# LAN.net
KiCad netlist of a schematic drawn in Altium Designer
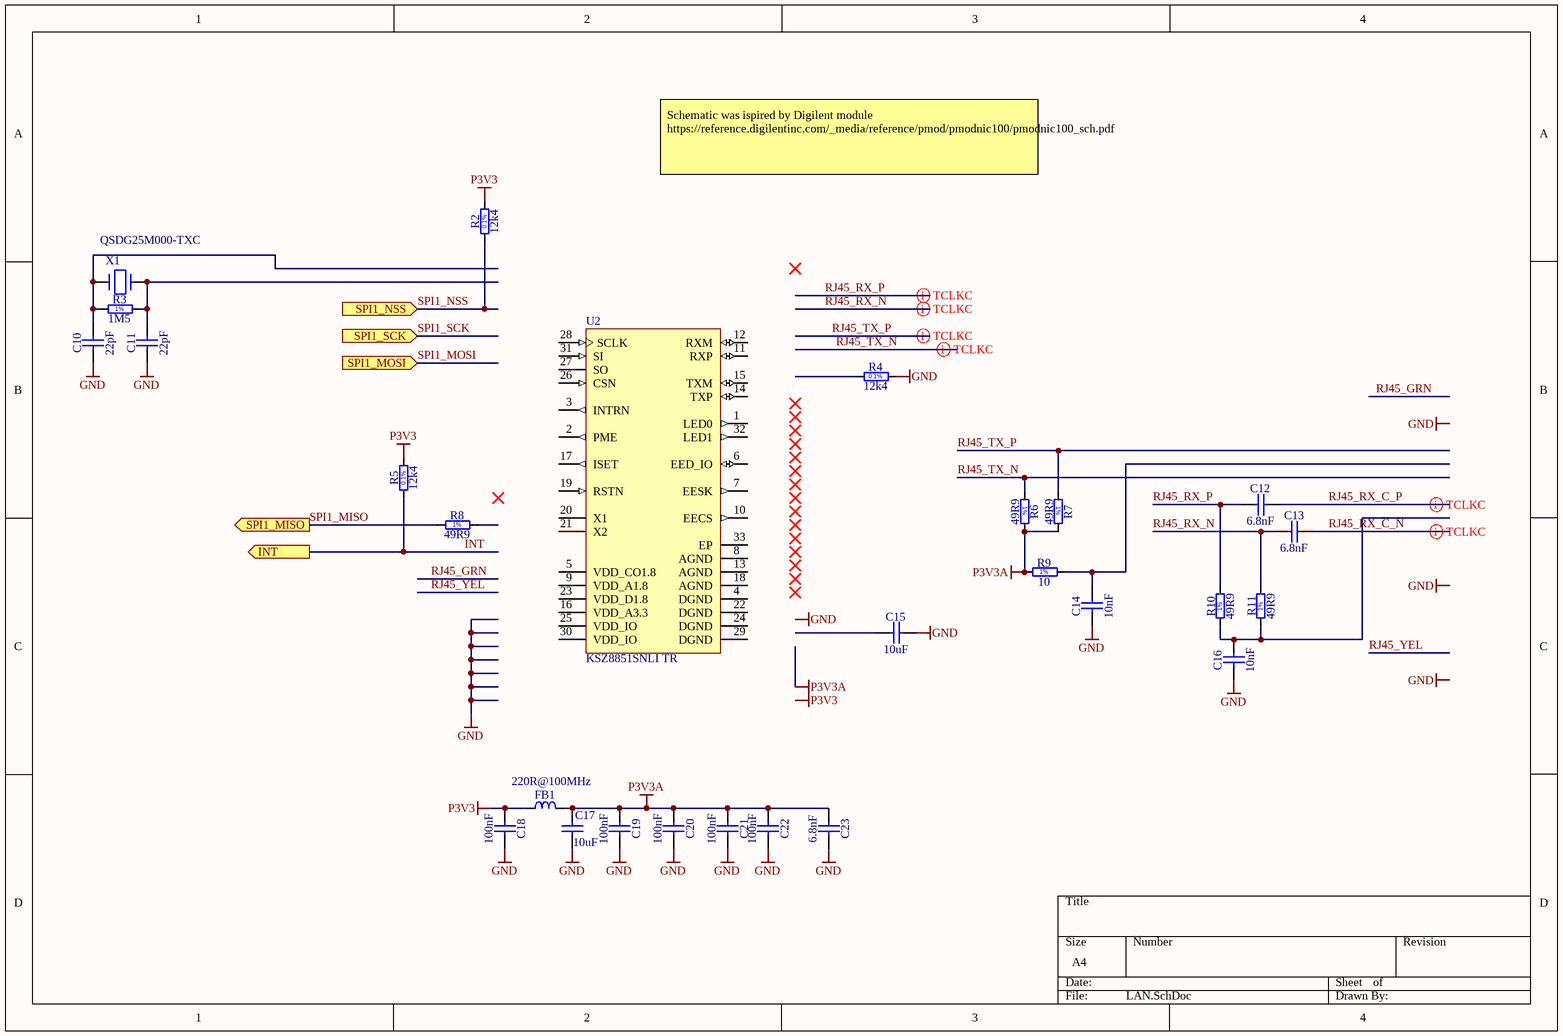
[diagram p0: LAN.SchDoc]

(export (version "E")
  (design (tool "Eeschema 10.0.6"))
  (components
    (comp (ref "C10")
      (value "22pF")
      (footprint "CAPC1005X55N")
      (description "Non-polarised capacitor")
      (fields
        (field (name "PART NUMBER") "CC0402_22PF_50V_5%_NP0")
        (field (name "VOLTAGE") "50V")
        (field (name "AUTHOR") "CERN DEM JLC")
      )
      (libsource (lib "Capacitors") (part "Capacitor - non polarized"))
    )
    (comp (ref "C11")
      (value "22pF")
      (footprint "CAPC1005X55N")
      (description "Non-polarised capacitor")
      (fields
        (field (name "PART NUMBER") "CC0402_22PF_50V_5%_NP0")
        (field (name "VOLTAGE") "50V")
        (field (name "AUTHOR") "CERN DEM JLC")
      )
      (libsource (lib "Capacitors") (part "Capacitor - non polarized"))
    )
    (comp (ref "C12")
      (value "6.8nF")
      (footprint "CAPC1608X87N")
      (description "Non-polarised capacitor")
      (fields
        (field (name "PART NUMBER") "CC0603_6.8NF_25V_1%_C0G")
        (field (name "VOLTAGE") "25V")
        (field (name "AUTHOR") "CERN DEM JLC")
      )
      (libsource (lib "Capacitors") (part "Capacitor - non polarized"))
    )
    (comp (ref "C13")
      (value "6.8nF")
      (footprint "CAPC1608X87N")
      (description "Non-polarised capacitor")
      (fields
        (field (name "PART NUMBER") "CC0603_6.8NF_25V_1%_C0G")
        (field (name "VOLTAGE") "25V")
        (field (name "AUTHOR") "CERN DEM JLC")
      )
      (libsource (lib "Capacitors") (part "Capacitor - non polarized"))
    )
    (comp (ref "C14")
      (value "10nF")
      (footprint "CAPC1608X87N")
      (description "Non-polarised capacitor")
      (fields
        (field (name "PART NUMBER") "CC0603_10NF_50V_5%_C0G")
        (field (name "VOLTAGE") "50V")
        (field (name "AUTHOR") "CERN DEM JLC")
      )
      (libsource (lib "Capacitors") (part "Capacitor - non polarized"))
    )
    (comp (ref "C15")
      (value "10uF")
      (footprint "CAPC1608X80N")
      (description "Non-polarised capacitor")
      (fields
        (field (name "PART NUMBER") "CC0603_10UF_16V_20%_X5R")
        (field (name "VOLTAGE") "16V")
        (field (name "AUTHOR") "CERN DEM MR")
      )
      (libsource (lib "Capacitors") (part "Capacitor - non polarized"))
    )
    (comp (ref "C16")
      (value "10nF")
      (footprint "CAPC1608X87N")
      (description "Non-polarised capacitor")
      (fields
        (field (name "PART NUMBER") "CC0603_10NF_50V_5%_C0G")
        (field (name "VOLTAGE") "50V")
        (field (name "AUTHOR") "CERN DEM JLC")
      )
      (libsource (lib "Capacitors") (part "Capacitor - non polarized"))
    )
    (comp (ref "C17")
      (value "10uF")
      (footprint "CAPC2012X135N")
      (description "Non-polarised capacitor")
      (fields
        (field (name "PART NUMBER") "CC0805_10UF_10V_10%_X7R")
        (field (name "VOLTAGE") "10V")
        (field (name "AUTHOR") "CERN DEM JLC")
      )
      (libsource (lib "Capacitors") (part "Capacitor - non polarized"))
    )
    (comp (ref "C18")
      (value "100nF")
      (footprint "CAPC1005X55N")
      (description "Non-polarised capacitor")
      (fields
        (field (name "PART NUMBER") "CC0402_100NF_16V_10%_X7R")
        (field (name "VOLTAGE") "16V")
        (field (name "AUTHOR") "CERN DEM JLC")
      )
      (libsource (lib "Capacitors") (part "Capacitor - non polarized"))
    )
    (comp (ref "C19")
      (value "100nF")
      (footprint "CAPC1005X55N")
      (description "Non-polarised capacitor")
      (fields
        (field (name "PART NUMBER") "CC0402_100NF_16V_10%_X7R")
        (field (name "VOLTAGE") "16V")
        (field (name "AUTHOR") "CERN DEM JLC")
      )
      (libsource (lib "Capacitors") (part "Capacitor - non polarized"))
    )
    (comp (ref "C20")
      (value "100nF")
      (footprint "CAPC1005X55N")
      (description "Non-polarised capacitor")
      (fields
        (field (name "PART NUMBER") "CC0402_100NF_16V_10%_X7R")
        (field (name "VOLTAGE") "16V")
        (field (name "AUTHOR") "CERN DEM JLC")
      )
      (libsource (lib "Capacitors") (part "Capacitor - non polarized"))
    )
    (comp (ref "C21")
      (value "100nF")
      (footprint "CAPC1005X55N")
      (description "Non-polarised capacitor")
      (fields
        (field (name "PART NUMBER") "CC0402_100NF_16V_10%_X7R")
        (field (name "VOLTAGE") "16V")
        (field (name "AUTHOR") "CERN DEM JLC")
      )
      (libsource (lib "Capacitors") (part "Capacitor - non polarized"))
    )
    (comp (ref "C22")
      (value "100nF")
      (footprint "CAPC1005X55N")
      (description "Non-polarised capacitor")
      (fields
        (field (name "PART NUMBER") "CC0402_100NF_16V_10%_X7R")
        (field (name "VOLTAGE") "16V")
        (field (name "AUTHOR") "CERN DEM JLC")
      )
      (libsource (lib "Capacitors") (part "Capacitor - non polarized"))
    )
    (comp (ref "C23")
      (value "6.8nF")
      (footprint "CAPC1608X87N")
      (description "Non-polarised capacitor")
      (fields
        (field (name "PART NUMBER") "CC0603_6.8NF_25V_1%_C0G")
        (field (name "VOLTAGE") "25V")
        (field (name "AUTHOR") "CERN DEM JLC")
      )
      (libsource (lib "Capacitors") (part "Capacitor - non polarized"))
    )
    (comp (ref "FB1")
      (value "220R@100MHz")
      (footprint "INDC2012X105N")
      (description "Inductor")
      (fields
        (field (name "PART NUMBER") "IND0805_MURATA_BLM21PG221SN1D")
        (field (name "POWER") "2A")
        (field (name "AUTHOR") "CERN DEM JLC")
      )
      (libsource (lib "Inductors & Transformers") (part "Inductor"))
    )
    (comp (ref "R2")
      (value "12k4")
      (footprint "RESC1608X55N")
      (description "Resistor - 0.1%")
      (fields
        (field (name "PART NUMBER") "R0603_12K4_0.1%_0.063W_10PPM")
        (field (name "POWER") "0.063W")
        (field (name "AUTHOR") "CERN DEM JLC")
      )
      (libsource (lib "Resistors") (part "Resistor - 0.1%"))
    )
    (comp (ref "R3")
      (value "1M5")
      (footprint "RESC1005X40N")
      (description "Resistor - 1%")
      (fields
        (field (name "PART NUMBER") "R0402_1M5_1%_0.0625W_100PPM")
        (field (name "POWER") "0.0625W")
        (field (name "AUTHOR") "CERN DEM JLC")
      )
      (libsource (lib "Resistors") (part "Resistor - 1%"))
    )
    (comp (ref "R4")
      (value "12k4")
      (footprint "RESC1608X55N")
      (description "Resistor - 0.1%")
      (fields
        (field (name "PART NUMBER") "R0603_12K4_0.1%_0.063W_10PPM")
        (field (name "POWER") "0.063W")
        (field (name "AUTHOR") "CERN DEM JLC")
      )
      (libsource (lib "Resistors") (part "Resistor - 0.1%"))
    )
    (comp (ref "R5")
      (value "12k4")
      (footprint "RESC1608X55N")
      (description "Resistor - 0.1%")
      (fields
        (field (name "PART NUMBER") "R0603_12K4_0.1%_0.063W_10PPM")
        (field (name "POWER") "0.063W")
        (field (name "AUTHOR") "CERN DEM JLC")
      )
      (libsource (lib "Resistors") (part "Resistor - 0.1%"))
    )
    (comp (ref "R6")
      (value "49R9")
      (footprint "RESC1005X40N")
      (description "Resistor - 1%")
      (fields
        (field (name "PART NUMBER") "R0402_49R9_1%_0.0625W_100PPM")
        (field (name "POWER") "0.0625W")
        (field (name "AUTHOR") "CERN DEM JLC")
      )
      (libsource (lib "Resistors") (part "Resistor - 1%"))
    )
    (comp (ref "R7")
      (value "49R9")
      (footprint "RESC1005X40N")
      (description "Resistor - 1%")
      (fields
        (field (name "PART NUMBER") "R0402_49R9_1%_0.0625W_100PPM")
        (field (name "POWER") "0.0625W")
        (field (name "AUTHOR") "CERN DEM JLC")
      )
      (libsource (lib "Resistors") (part "Resistor - 1%"))
    )
    (comp (ref "R8")
      (value "49R9")
      (footprint "RESC1005X40N")
      (description "Resistor - 1%")
      (fields
        (field (name "PART NUMBER") "R0402_49R9_1%_0.0625W_100PPM")
        (field (name "POWER") "0.0625W")
        (field (name "AUTHOR") "CERN DEM JLC")
      )
      (libsource (lib "Resistors") (part "Resistor - 1%"))
    )
    (comp (ref "R9")
      (value "10")
      (footprint "RESC1005X40N")
      (description "Resistor - 1%")
      (fields
        (field (name "PART NUMBER") "R0402_10R_1%_0.0625W_200PPM")
        (field (name "POWER") "0.0625W")
        (field (name "AUTHOR") "CERN DEM JLC")
      )
      (libsource (lib "Resistors") (part "Resistor - 1%"))
    )
    (comp (ref "R10")
      (value "49R9")
      (footprint "RESC1005X40N")
      (description "Resistor - 1%")
      (fields
        (field (name "PART NUMBER") "R0402_49R9_1%_0.0625W_100PPM")
        (field (name "POWER") "0.0625W")
        (field (name "AUTHOR") "CERN DEM JLC")
      )
      (libsource (lib "Resistors") (part "Resistor - 1%"))
    )
    (comp (ref "R11")
      (value "49R9")
      (footprint "RESC1005X40N")
      (description "Resistor - 1%")
      (fields
        (field (name "PART NUMBER") "R0402_49R9_1%_0.0625W_100PPM")
        (field (name "POWER") "0.0625W")
        (field (name "AUTHOR") "CERN DEM JLC")
      )
      (libsource (lib "Resistors") (part "Resistor - 1%"))
    )
    (comp (ref "U2")
      (value "KSZ8851SNLI TR")
      (footprint "MCHP-MLF-32_L")
      (fields (field (name "MANUFACTURER") "Micrel"))
      (libsource (lib "Altium Content Vault") (part "MCHP-KSZ8851SNL-MLF-32"))
    )
    (comp (ref "X1")
      (value "QSDG25M000-TXC")
      (footprint "XTAL_5.0*3.2")
      (description "miniature crystal oscillator (Maritex)")
      (libsource (lib "LIBRARY_SCH") (part "X_CRYSTAL_SMD_5.0*3.2"))
    )
  )
  (nets
    (net (code "1") (name "/INT") (class "Default")
      (node (ref "R5") (pin "1") (pinfunction "1_1") (pintype "passive"))
    )
    (net (code "3") (name "/RJ45_RX_C_N") (class "Default")
      (node (ref "C13") (pin "2") (pinfunction "2_2") (pintype "passive"))
    )
    (net (code "4") (name "/RJ45_RX_C_P") (class "Default")
      (node (ref "C12") (pin "2") (pinfunction "2_2") (pintype "passive"))
    )
    (net (code "5") (name "/RJ45_RX_N") (class "Default")
      (node (ref "C13") (pin "1") (pinfunction "1_1") (pintype "passive"))
      (node (ref "R11") (pin "2") (pinfunction "2_2") (pintype "passive"))
    )
    (net (code "6") (name "/RJ45_RX_P") (class "Default")
      (node (ref "C12") (pin "1") (pinfunction "1_1") (pintype "passive"))
      (node (ref "R10") (pin "2") (pinfunction "2_2") (pintype "passive"))
    )
    (net (code "7") (name "/RJ45_TX_N") (class "Default")
      (node (ref "R6") (pin "1") (pinfunction "1_1") (pintype "passive"))
    )
    (net (code "8") (name "/RJ45_TX_P") (class "Default")
      (node (ref "R7") (pin "1") (pinfunction "1_1") (pintype "passive"))
    )
    (net (code "10") (name "/SPI1_MISO") (class "Default")
      (node (ref "R8") (pin "1") (pinfunction "1_1") (pintype "passive"))
    )
    (net (code "12") (name "/SPI1_NSS") (class "Default")
      (node (ref "R2") (pin "1") (pinfunction "1_1") (pintype "passive"))
    )
    (net (code "14") (name "GND") (class "Default")
      (node (ref "C10") (pin "1") (pinfunction "1_1") (pintype "passive"))
      (node (ref "C11") (pin "1") (pinfunction "1_1") (pintype "passive"))
      (node (ref "C14") (pin "1") (pinfunction "1_1") (pintype "passive"))
      (node (ref "C15") (pin "2") (pinfunction "2_2") (pintype "passive"))
      (node (ref "C16") (pin "1") (pinfunction "1_1") (pintype "passive"))
      (node (ref "C17") (pin "2") (pinfunction "2_2") (pintype "passive"))
      (node (ref "C18") (pin "2") (pinfunction "2_2") (pintype "passive"))
      (node (ref "C19") (pin "2") (pinfunction "2_2") (pintype "passive"))
      (node (ref "C20") (pin "2") (pinfunction "2_2") (pintype "passive"))
      (node (ref "C21") (pin "2") (pinfunction "2_2") (pintype "passive"))
      (node (ref "C22") (pin "2") (pinfunction "2_2") (pintype "passive"))
      (node (ref "C23") (pin "2") (pinfunction "2_2") (pintype "passive"))
      (node (ref "R4") (pin "2") (pinfunction "2_2") (pintype "passive"))
    )
    (net (code "15") (name "Net-(C10-Pad2)") (class "Default")
      (node (ref "C10") (pin "2") (pinfunction "2_2") (pintype "passive"))
      (node (ref "R3") (pin "1") (pinfunction "1_1") (pintype "passive"))
      (node (ref "X1") (pin "1") (pinfunction "1_1") (pintype "passive"))
    )
    (net (code "16") (name "Net-(C11-Pad2)") (class "Default")
      (node (ref "C11") (pin "2") (pinfunction "2_2") (pintype "passive"))
      (node (ref "R3") (pin "2") (pinfunction "2_2") (pintype "passive"))
      (node (ref "X1") (pin "2") (pinfunction "2_2") (pintype "passive"))
    )
    (net (code "17") (name "Net-(C14-Pad2)") (class "Default")
      (node (ref "C14") (pin "2") (pinfunction "2_2") (pintype "passive"))
      (node (ref "R9") (pin "2") (pinfunction "2_2") (pintype "passive"))
    )
    (net (code "18") (name "Net-(C16-Pad2)") (class "Default")
      (node (ref "C16") (pin "2") (pinfunction "2_2") (pintype "passive"))
      (node (ref "R10") (pin "1") (pinfunction "1_1") (pintype "passive"))
      (node (ref "R11") (pin "1") (pinfunction "1_1") (pintype "passive"))
    )
    (net (code "19") (name "P3V3") (class "Default")
      (node (ref "C18") (pin "1") (pinfunction "1_1") (pintype "passive"))
      (node (ref "FB1") (pin "1") (pinfunction "1_1") (pintype "passive"))
      (node (ref "R2") (pin "2") (pinfunction "2_2") (pintype "passive"))
      (node (ref "R5") (pin "2") (pinfunction "2_2") (pintype "passive"))
    )
    (net (code "20") (name "P3V3A") (class "Default")
      (node (ref "C17") (pin "1") (pinfunction "1_1") (pintype "passive"))
      (node (ref "C19") (pin "1") (pinfunction "1_1") (pintype "passive"))
      (node (ref "C20") (pin "1") (pinfunction "1_1") (pintype "passive"))
      (node (ref "C21") (pin "1") (pinfunction "1_1") (pintype "passive"))
      (node (ref "C22") (pin "1") (pinfunction "1_1") (pintype "passive"))
      (node (ref "C23") (pin "1") (pinfunction "1_1") (pintype "passive"))
      (node (ref "FB1") (pin "2") (pinfunction "2_2") (pintype "passive"))
      (node (ref "R6") (pin "2") (pinfunction "2_2") (pintype "passive"))
      (node (ref "R7") (pin "2") (pinfunction "2_2") (pintype "passive"))
      (node (ref "R9") (pin "1") (pinfunction "1_1") (pintype "passive"))
    )
    (net (code "21") (name "unconnected-(C15-Pad1)") (class "Default")
      (node (ref "C15") (pin "1") (pinfunction "1_1") (pintype "passive"))
    )
    (net (code "22") (name "unconnected-(R4-Pad1)") (class "Default")
      (node (ref "R4") (pin "1") (pinfunction "1_1") (pintype "passive"))
    )
    (net (code "23") (name "unconnected-(R8-Pad2)") (class "Default")
      (node (ref "R8") (pin "2") (pinfunction "2_2") (pintype "passive"))
    )
    (net (code "24") (name "unconnected-(U2-AGND-Pad8)") (class "Default")
      (node (ref "U2") (pin "8") (pinfunction "AGND_8") (pintype "power_in"))
    )
    (net (code "25") (name "unconnected-(U2-AGND-Pad13)") (class "Default")
      (node (ref "U2") (pin "13") (pinfunction "AGND_13") (pintype "power_in"))
    )
    (net (code "26") (name "unconnected-(U2-AGND-Pad18)") (class "Default")
      (node (ref "U2") (pin "18") (pinfunction "AGND_18") (pintype "power_in"))
    )
    (net (code "27") (name "unconnected-(U2-CSN-Pad26)") (class "Default")
      (node (ref "U2") (pin "26") (pinfunction "CSN_26") (pintype "input"))
    )
    (net (code "28") (name "unconnected-(U2-DGND-Pad4)") (class "Default")
      (node (ref "U2") (pin "4") (pinfunction "DGND_4") (pintype "power_in"))
    )
    (net (code "29") (name "unconnected-(U2-DGND-Pad22)") (class "Default")
      (node (ref "U2") (pin "22") (pinfunction "DGND_22") (pintype "power_in"))
    )
    (net (code "30") (name "unconnected-(U2-DGND-Pad24)") (class "Default")
      (node (ref "U2") (pin "24") (pinfunction "DGND_24") (pintype "power_in"))
    )
    (net (code "31") (name "unconnected-(U2-DGND-Pad29)") (class "Default")
      (node (ref "U2") (pin "29") (pinfunction "DGND_29") (pintype "power_in"))
    )
    (net (code "32") (name "unconnected-(U2-EECS-Pad10)") (class "Default")
      (node (ref "U2") (pin "10") (pinfunction "EECS_10") (pintype "output"))
    )
    (net (code "33") (name "unconnected-(U2-EED_IO-Pad6)") (class "Default")
      (node (ref "U2") (pin "6") (pinfunction "EED_IO_6") (pintype "bidirectional"))
    )
    (net (code "34") (name "unconnected-(U2-EESK-Pad7)") (class "Default")
      (node (ref "U2") (pin "7") (pinfunction "EESK_7") (pintype "output"))
    )
    (net (code "35") (name "unconnected-(U2-EP-Pad33)") (class "Default")
      (node (ref "U2") (pin "33") (pinfunction "EP_33") (pintype "power_in"))
    )
    (net (code "36") (name "unconnected-(U2-INTRN-Pad3)") (class "Default")
      (node (ref "U2") (pin "3") (pinfunction "INTRN_3") (pintype "output"))
    )
    (net (code "37") (name "unconnected-(U2-ISET-Pad17)") (class "Default")
      (node (ref "U2") (pin "17") (pinfunction "ISET_17") (pintype "output"))
    )
    (net (code "38") (name "unconnected-(U2-LED0-Pad1)") (class "Default")
      (node (ref "U2") (pin "1") (pinfunction "LED0_1") (pintype "output"))
    )
    (net (code "39") (name "unconnected-(U2-LED1-Pad32)") (class "Default")
      (node (ref "U2") (pin "32") (pinfunction "LED1_32") (pintype "output"))
    )
    (net (code "40") (name "unconnected-(U2-PME-Pad2)") (class "Default")
      (node (ref "U2") (pin "2") (pinfunction "PME_2") (pintype "output"))
    )
    (net (code "41") (name "unconnected-(U2-RSTN-Pad19)") (class "Default")
      (node (ref "U2") (pin "19") (pinfunction "RSTN_19") (pintype "input"))
    )
    (net (code "42") (name "unconnected-(U2-RXM-Pad12)") (class "Default")
      (node (ref "U2") (pin "12") (pinfunction "RXM_12") (pintype "bidirectional"))
    )
    (net (code "43") (name "unconnected-(U2-RXP-Pad11)") (class "Default")
      (node (ref "U2") (pin "11") (pinfunction "RXP_11") (pintype "bidirectional"))
    )
    (net (code "44") (name "unconnected-(U2-SCLK-Pad28)") (class "Default")
      (node (ref "U2") (pin "28") (pinfunction "SCLK_28") (pintype "input"))
    )
    (net (code "45") (name "unconnected-(U2-SI-Pad31)") (class "Default")
      (node (ref "U2") (pin "31") (pinfunction "SI_31") (pintype "input"))
    )
    (net (code "46") (name "unconnected-(U2-SO-Pad27)") (class "Default")
      (node (ref "U2") (pin "27") (pinfunction "SO_27") (pintype "tri_state"))
    )
    (net (code "47") (name "unconnected-(U2-TXM-Pad15)") (class "Default")
      (node (ref "U2") (pin "15") (pinfunction "TXM_15") (pintype "bidirectional"))
    )
    (net (code "48") (name "unconnected-(U2-TXP-Pad14)") (class "Default")
      (node (ref "U2") (pin "14") (pinfunction "TXP_14") (pintype "bidirectional"))
    )
    (net (code "49") (name "unconnected-(U2-VDD_A1.8-Pad9)") (class "Default")
      (node (ref "U2") (pin "9") (pinfunction "VDD_A1.8_9") (pintype "power_in"))
    )
    (net (code "50") (name "unconnected-(U2-VDD_A3.3-Pad16)") (class "Default")
      (node (ref "U2") (pin "16") (pinfunction "VDD_A3.3_16") (pintype "power_in"))
    )
    (net (code "51") (name "unconnected-(U2-VDD_CO1.8-Pad5)") (class "Default")
      (node (ref "U2") (pin "5") (pinfunction "VDD_CO1.8_5") (pintype "power_in"))
    )
    (net (code "52") (name "unconnected-(U2-VDD_D1.8-Pad23)") (class "Default")
      (node (ref "U2") (pin "23") (pinfunction "VDD_D1.8_23") (pintype "power_in"))
    )
    (net (code "53") (name "unconnected-(U2-VDD_IO-Pad25)") (class "Default")
      (node (ref "U2") (pin "25") (pinfunction "VDD_IO_25") (pintype "power_in"))
    )
    (net (code "54") (name "unconnected-(U2-VDD_IO-Pad30)") (class "Default")
      (node (ref "U2") (pin "30") (pinfunction "VDD_IO_30") (pintype "power_in"))
    )
    (net (code "55") (name "unconnected-(U2-X1-Pad20)") (class "Default")
      (node (ref "U2") (pin "20") (pinfunction "X1_20") (pintype "passive"))
    )
    (net (code "56") (name "unconnected-(U2-X2-Pad21)") (class "Default")
      (node (ref "U2") (pin "21") (pinfunction "X2_21") (pintype "passive"))
    )
  )
)
